# P01R0.net
KiCad netlist of a schematic drawn in EAGLE
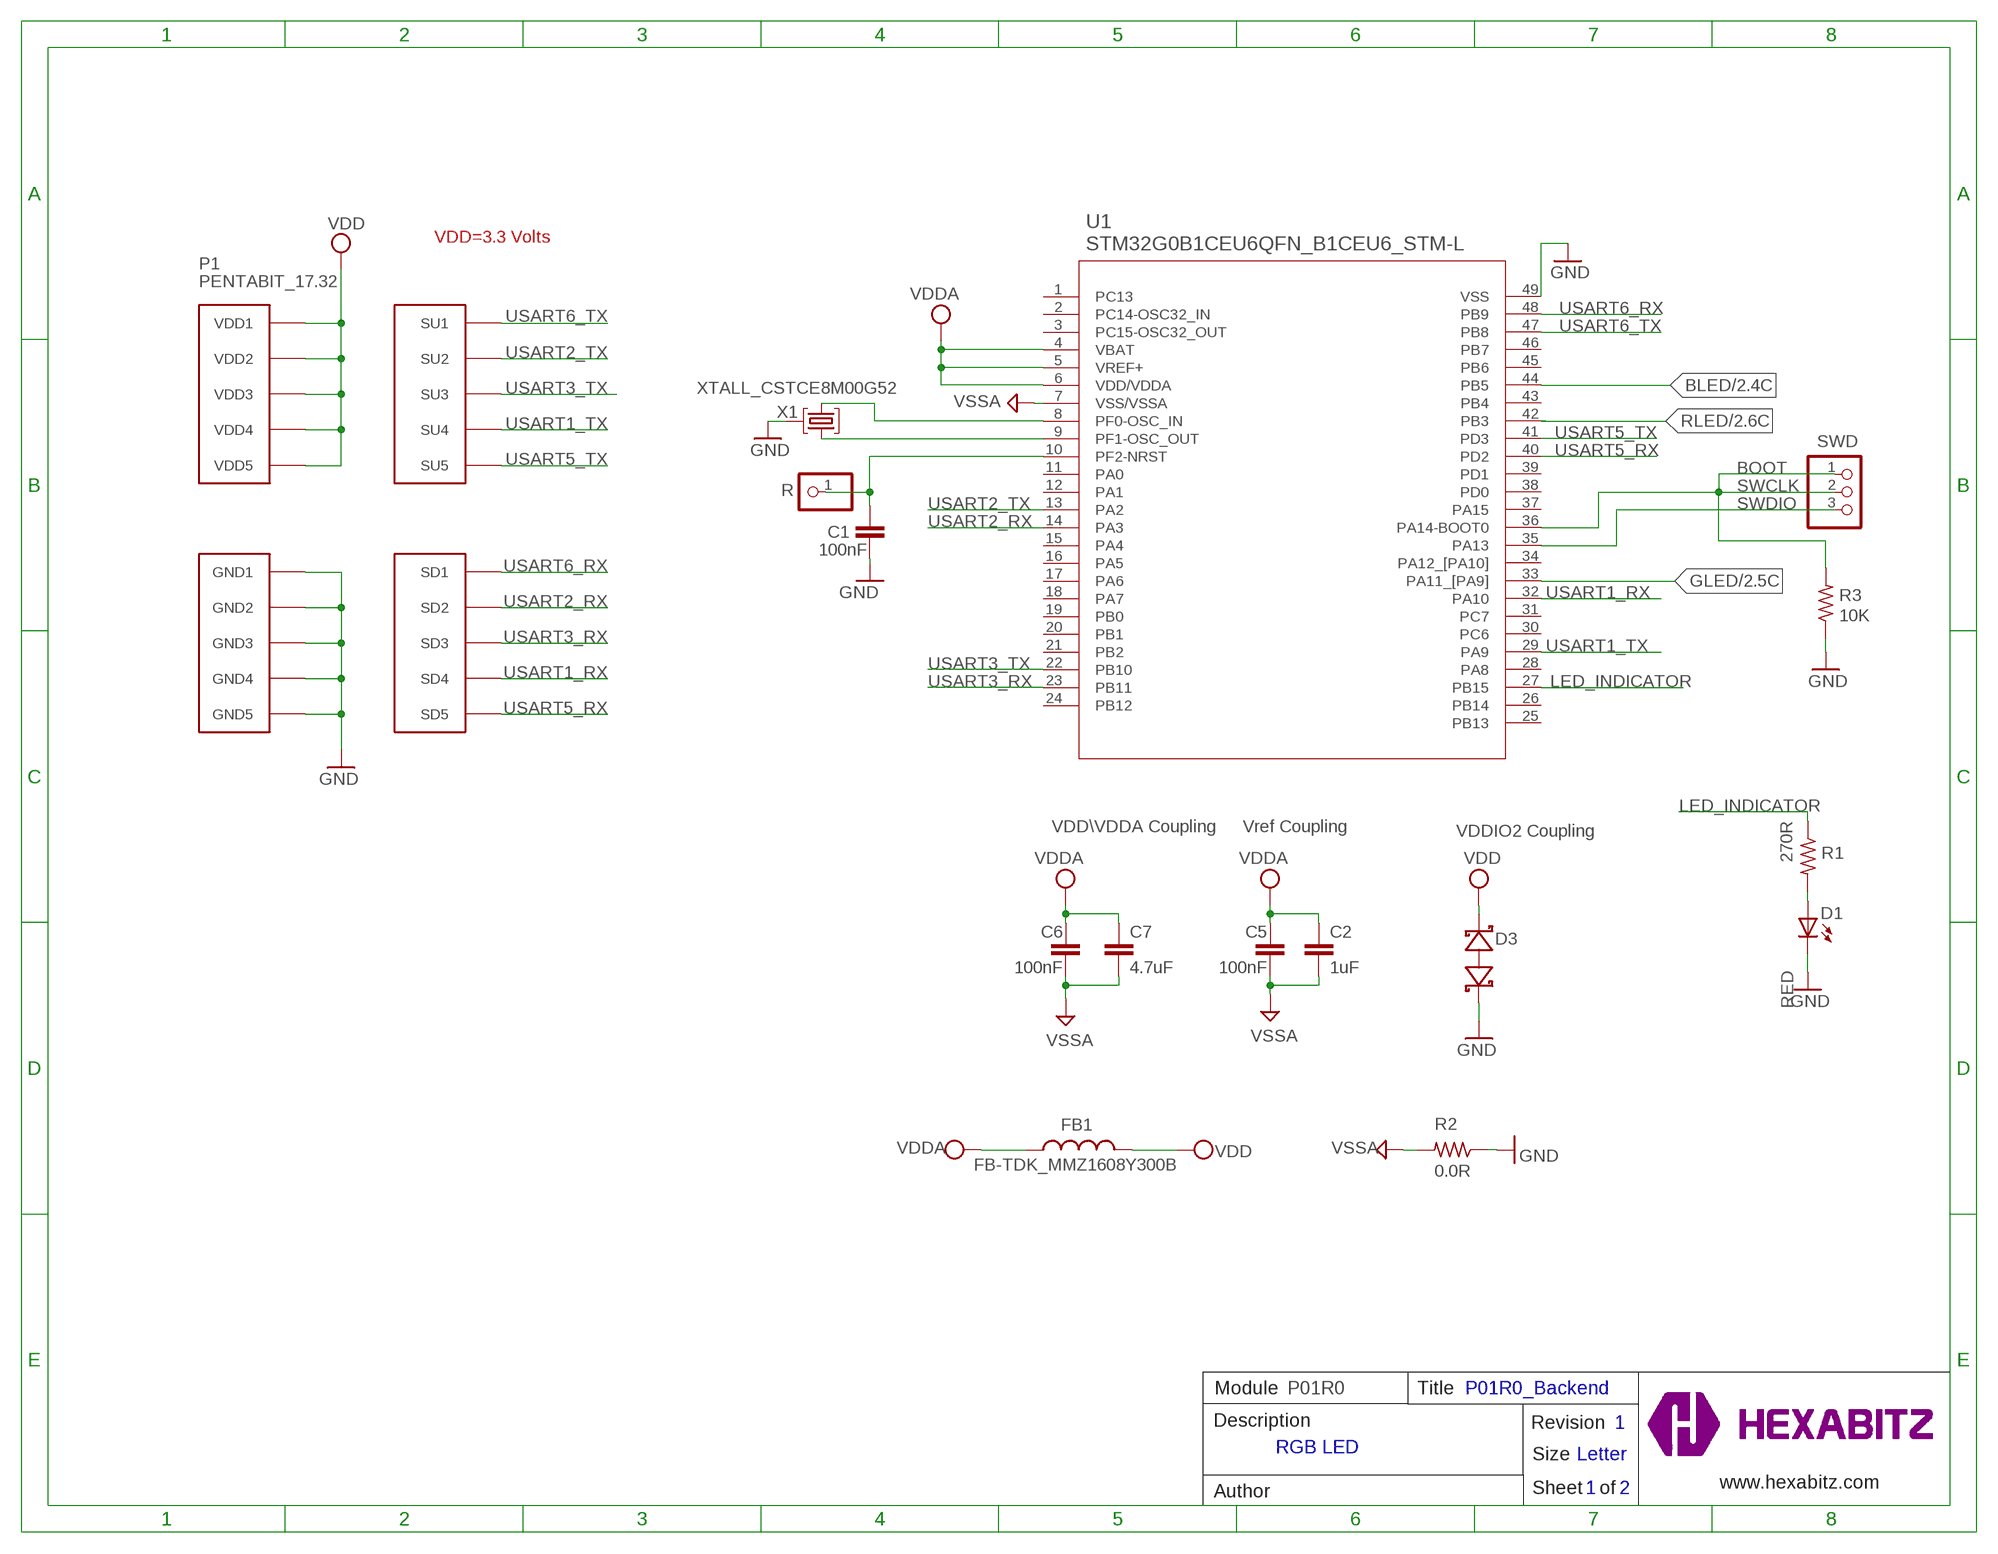
[diagram p0: schematic, sheet 1]
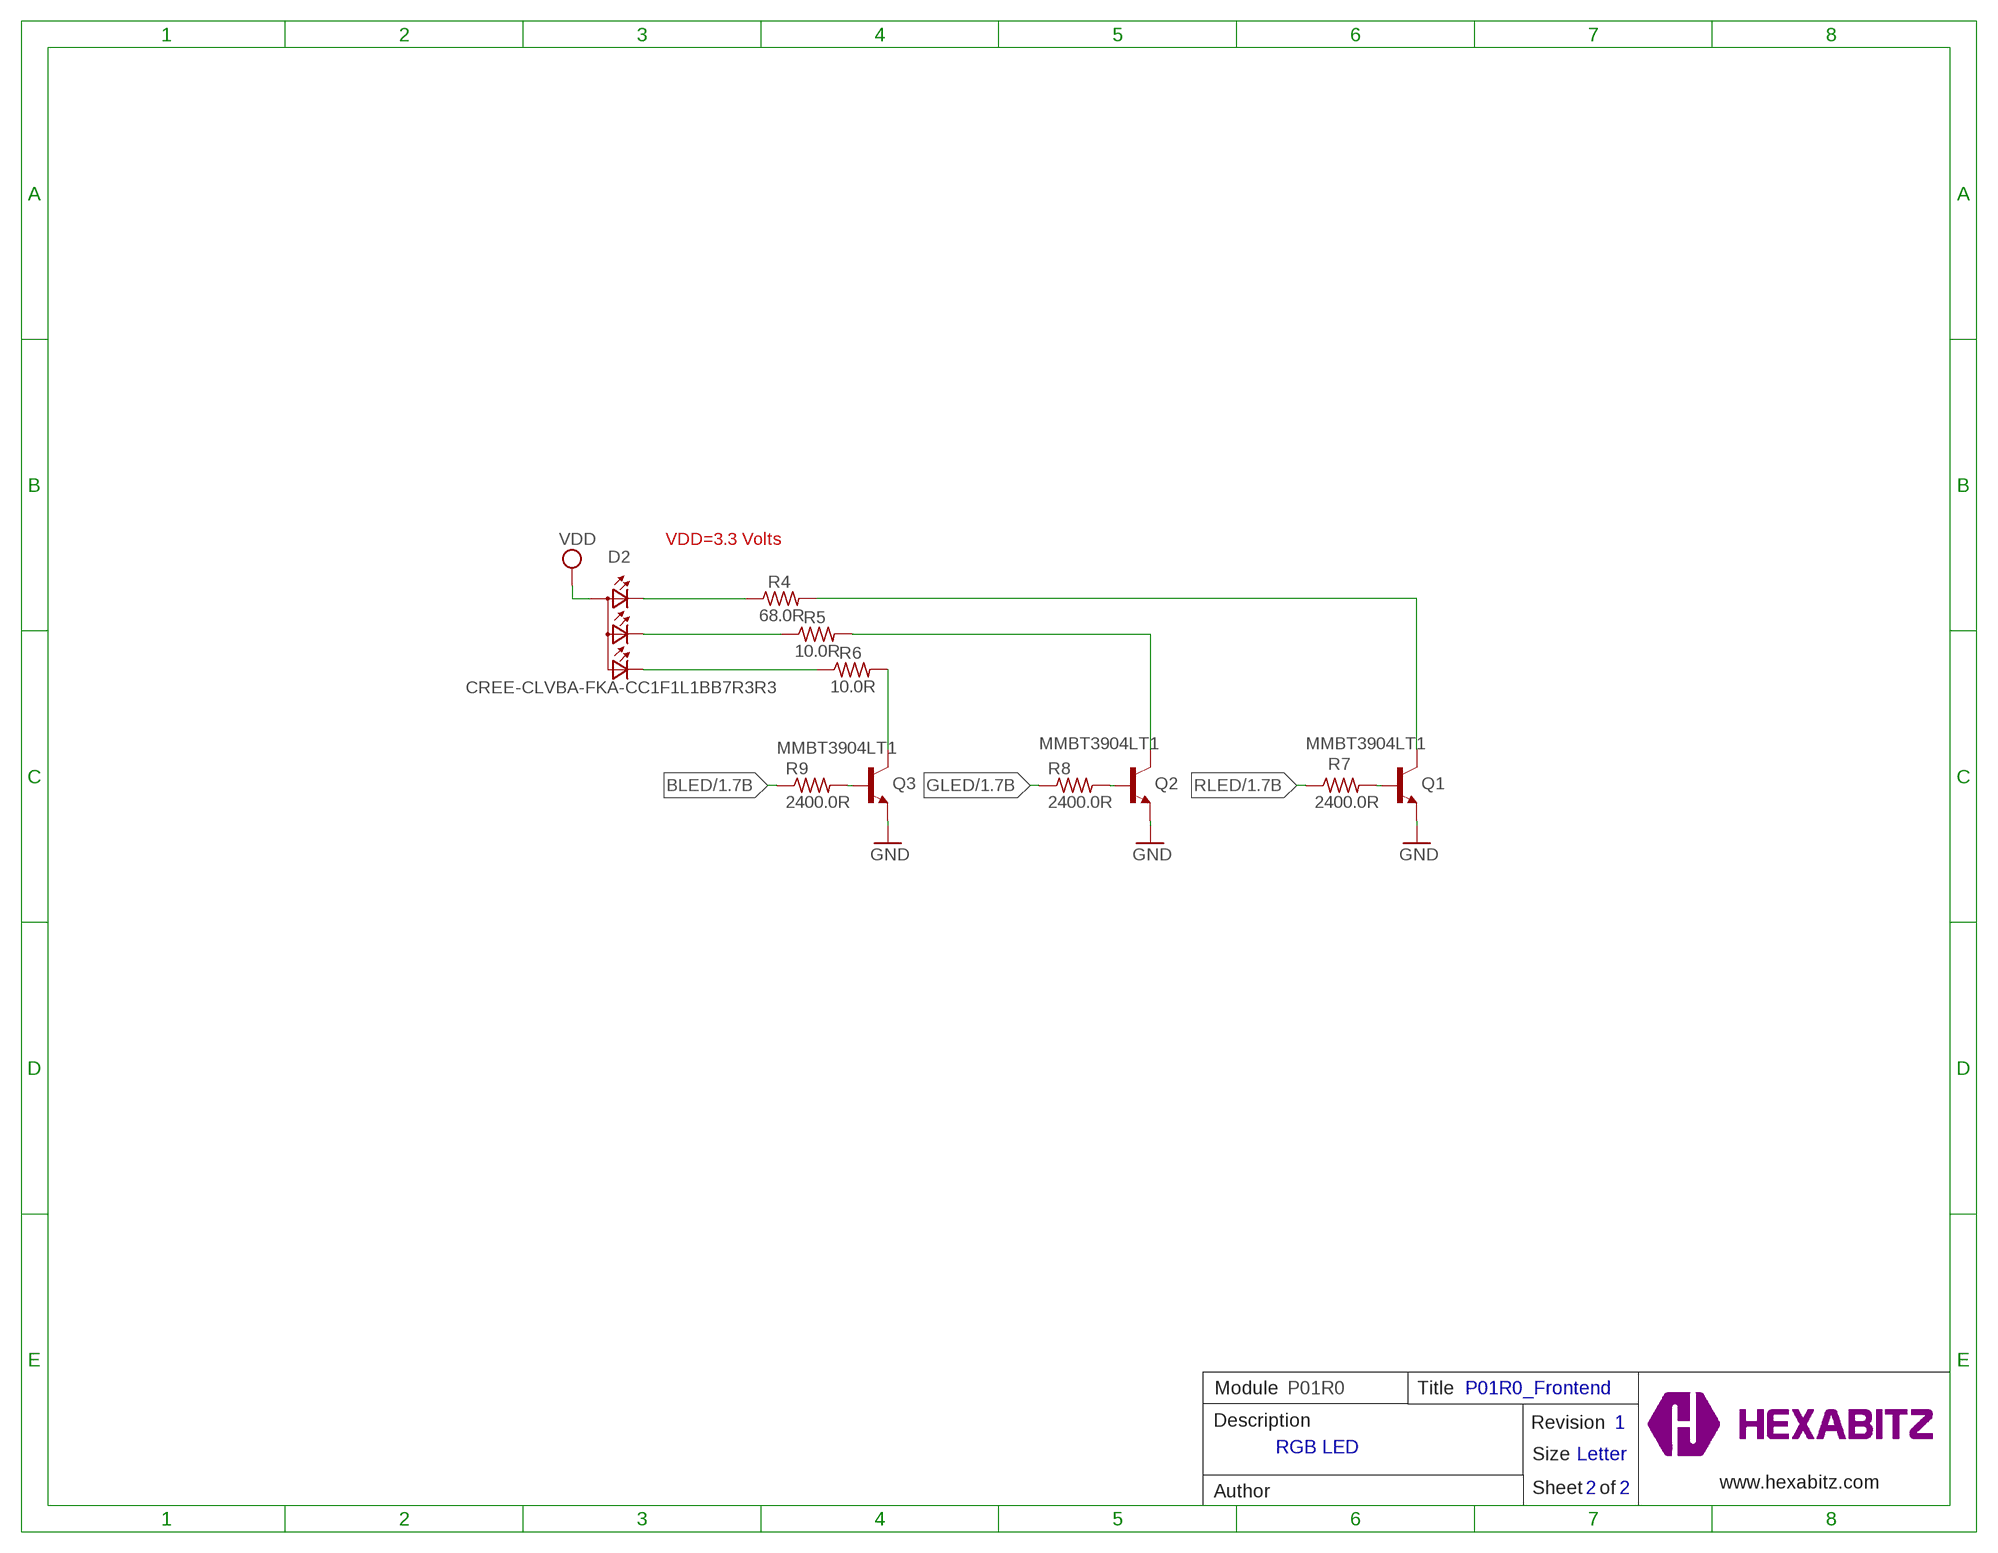
[diagram p1: schematic, sheet 2]

(export (version "E")
  (design (tool "Eeschema 10.0.6"))
  (components
    (comp (ref "C1")
      (value "100nF")
      (footprint "eagle-import:C-0603")
      (libsource (lib "eagle-import") (part "C-0603"))
    )
    (comp (ref "C2")
      (value "1uF")
      (footprint "eagle-import:C-0805")
      (libsource (lib "eagle-import") (part "C-0805"))
    )
    (comp (ref "C5")
      (value "100nF")
      (footprint "eagle-import:C-0603")
      (libsource (lib "eagle-import") (part "C-0603"))
    )
    (comp (ref "C6")
      (value "100nF")
      (footprint "eagle-import:C-0603")
      (libsource (lib "eagle-import") (part "C-0603"))
    )
    (comp (ref "C7")
      (value "4.7uF")
      (footprint "eagle-import:C-0805")
      (libsource (lib "eagle-import") (part "C-0805"))
    )
    (comp (ref "D1")
      (value "RED")
      (footprint "eagle-import:VLMS1300-GS08")
      (fields
        (field (name "MPN") "VLMS1300-GS08")
        (field (name "MFN") "Vishay")
        (field (name "MPN_1") "VLMS1300-GS08")
        (field (name "OCTOPART_URL") "https://octopart.com/vlms1300-gs08-vishay-21709201?r=sp&s=_gcP4_q8T1SC6PJQPTQ9yA")
      )
      (libsource (lib "eagle-import") (part "VLMS1300-GS08"))
    )
    (comp (ref "D3")
      (value "BOURNS_CDSOD323-T03SCBOURNS_CDSOD323-T03SC_0_0")
      (footprint "eagle-import:BOURNS_CDSOD323-T03SC_0")
      (fields (field (name "MPN") "CDSOD323-T03SC"))
      (libsource (lib "eagle-import") (part "BOURNS_CDSOD323-T03SCBOURNS_CDSOD323-T03SC_0_0"))
    )
    (comp (ref "FB1")
      (value "FB-TDK_MMZ1608Y300B")
      (footprint "eagle-import:FB-0603")
      (fields
        (field (name "MFN") "TDK ")
        (field (name "MPN") "MMZ1608Y300B")
        (field (name "OCTOPART_URL") "https://octopart.com/mmz1608y300b-tdk-368280?r=sp&s=cd9_2ZEqQ9q9UNBuQgHAiA")
      )
      (libsource (lib "eagle-import") (part "FB-0603"))
    )
    (comp (ref "P1")
      (value "PENTABIT_17.32")
      (footprint "eagle-import:PENTABIT_17.32")
      (libsource (lib "eagle-import") (part "PENTABIT_?17.32"))
    )
    (comp (ref "R")
      (value "R")
      (footprint "eagle-import:1X01")
      (fields (field (name "MPN") "87227-1"))
      (libsource (lib "eagle-import") (part "PINHD-1X1"))
    )
    (comp (ref "R1")
      (value "270R")
      (footprint "eagle-import:R-0603")
      (libsource (lib "eagle-import") (part "R-0603"))
    )
    (comp (ref "R2")
      (value "0.0R")
      (footprint "eagle-import:R-0603")
      (fields
        (field (name "MFN") "Yageo")
        (field (name "MPN") "RC0603JR-070RL")
        (field (name "OCTOPART_URL") "https://octopart.com/rc0603jr-070rl-yageo-1241539?r=sp&s=X2NteqRjRNWrnx42Y0aliA")
        (field (name "RESISTANCE") "0.0 Ohm")
      )
      (libsource (lib "eagle-import") (part "R-0603"))
    )
    (comp (ref "R3")
      (value "10K")
      (footprint "eagle-import:R-0603")
      (libsource (lib "eagle-import") (part "R-0603"))
    )
    (comp (ref "SWD")
      (value "PINHD-1X3")
      (footprint "eagle-import:1X03")
      (libsource (lib "eagle-import") (part "PINHD-1X3"))
    )
    (comp (ref "U1")
      (value "STM32G0B1CEU6QFN_B1CEU6_STM-L")
      (footprint "eagle-import:QFN_B1CEU6_STM-L")
      (fields
        (field (name "MANUFACTURER_PART_NUMBER") "STM32G0B1CEU6")
        (field (name "COPYRIGHT") "Copyright (C) 2021 Ultra Librarian. All rights reserved.")
      )
      (libsource (lib "eagle-import") (part "STM32G0B1CEU6QFN_B1CEU6_STM-L"))
    )
    (comp (ref "X1")
      (value "XTALL_CSTCE8M00G52")
      (footprint "eagle-import:XTALL_CSTCE8M00G52")
      (fields (field (name "MPN") "CSTCE8M00G52Z-R0"))
      (libsource (lib "eagle-import") (part "XTALL_CSTCE8M00G52"))
    )
    (comp (ref "D2")
      (value "CREE-CLVBA-FKA-CC1F1L1BB7R3R3")
      (footprint "eagle-import:PCB-1023943-1")
      (fields (field (name "MPN") "CLVBA-FKA-CC1F1L1BB7R3R3"))
      (libsource (lib "eagle-import") (part "CREE-CLVBA-FKA-CC1F1L1BB7R3R3"))
    )
    (comp (ref "Q1")
      (value "MMBT3904LT1")
      (footprint "eagle-import:MMBT3904LT1")
      (fields
        (field (name "OCTOPART_ID") "0bb6c2bc2200d471")
        (field (name "OCTOPART_URL") "http://octopart.com/mmbt3904lt1g-on+semiconductor-3280")
        (field (name "POLARITY") "NPN")
        (field (name "POWER_DISSIPATION") "0.225W")
        (field (name "VOLTAGE_RATING_DC") "40.0V")
      )
      (libsource (lib "eagle-import") (part "MMBT3904LT1"))
    )
    (comp (ref "Q2")
      (value "MMBT3904LT1")
      (footprint "eagle-import:MMBT3904LT1")
      (fields
        (field (name "OCTOPART_ID") "0bb6c2bc2200d471")
        (field (name "OCTOPART_URL") "http://octopart.com/mmbt3904lt1g-on+semiconductor-3280")
        (field (name "POLARITY") "NPN")
        (field (name "POWER_DISSIPATION") "0.225W")
        (field (name "VOLTAGE_RATING_DC") "40.0V")
      )
      (libsource (lib "eagle-import") (part "MMBT3904LT1"))
    )
    (comp (ref "Q3")
      (value "MMBT3904LT1")
      (footprint "eagle-import:MMBT3904LT1")
      (fields
        (field (name "MFN") "ON Semiconductor")
        (field (name "MPN") "MMBT3904LT1G")
        (field (name "OCTOPART_ID") "0bb6c2bc2200d471")
        (field (name "OCTOPART_URL") "http://octopart.com/mmbt3904lt1g-on+semiconductor-3280")
        (field (name "POLARITY") "NPN")
        (field (name "POWER_DISSIPATION") "0.225W")
        (field (name "VOLTAGE_RATING_DC") "40.0V")
      )
      (libsource (lib "eagle-import") (part "MMBT3904LT1"))
    )
    (comp (ref "R4")
      (value "68.0R")
      (footprint "eagle-import:R-0603")
      (fields
        (field (name "MFN") "Vishay")
        (field (name "MPN") "CRCW060368R0FKEA")
        (field (name "OCTOPART_URL") "https://octopart.com/crcw060368r0fkea-vishay-39811903")
        (field (name "RESISTANCE") "68.0 Ω")
        (field (name "SPICEPREFIX") "R")
        (field (name "TOLERANCE") "1%")
      )
      (libsource (lib "eagle-import") (part "R-0603"))
    )
    (comp (ref "R5")
      (value "10.0R")
      (footprint "eagle-import:R-0603")
      (fields
        (field (name "MFN") "Vishay")
        (field (name "MPN") "CRCW060310R0FKEB")
        (field (name "OCTOPART_URL") "https://octopart.com/crcw060310r0fkeb-vishay-42507905")
        (field (name "RESISTANCE") "10.0 Ω")
        (field (name "TOLERANCE") "1%")
      )
      (libsource (lib "eagle-import") (part "R-0603"))
    )
    (comp (ref "R6")
      (value "10.0R")
      (footprint "eagle-import:R-0603")
      (fields
        (field (name "MFN") "Vishay")
        (field (name "MPN") "CRCW060310R0FKEB")
        (field (name "OCTOPART_URL") "https://octopart.com/crcw060310r0fkeb-vishay-42507905")
        (field (name "RESISTANCE") "10.0 Ω")
        (field (name "TOLERANCE") "1%")
      )
      (libsource (lib "eagle-import") (part "R-0603"))
    )
    (comp (ref "R7")
      (value "2400.0R")
      (footprint "eagle-import:R-0603")
      (fields
        (field (name "MFN") "Vishay")
        (field (name "MPN") "CRCW06032K40JNEA")
        (field (name "OCTOPART_URL") "https://octopart.com/crcw06032k40jnea-vishay-40298967")
        (field (name "RESISTANCE") "2400.0 Ω")
        (field (name "TOLERANCE") "5%")
      )
      (libsource (lib "eagle-import") (part "R-0603"))
    )
    (comp (ref "R8")
      (value "2400.0R")
      (footprint "eagle-import:R-0603")
      (fields
        (field (name "MFN") "Vishay")
        (field (name "MPN") "CRCW06032K40JNEA")
        (field (name "OCTOPART_URL") "https://octopart.com/crcw06032k40jnea-vishay-40298967")
        (field (name "RESISTANCE") "2400.0 Ω")
        (field (name "TOLERANCE") "5%")
      )
      (libsource (lib "eagle-import") (part "R-0603"))
    )
    (comp (ref "R9")
      (value "2400.0R")
      (footprint "eagle-import:R-0603")
      (fields
        (field (name "MFN") "Vishay")
        (field (name "MPN") "CRCW06032K40JNEA")
        (field (name "OCTOPART_URL") "https://octopart.com/crcw06032k40jnea-vishay-40298967")
        (field (name "TOLERANCE") "5%")
      )
      (libsource (lib "eagle-import") (part "R-0603"))
    )
    (comp (ref "TRIMBLE-LOGO1")
      (value "HEXA-LOGO")
      (footprint "eagle-import:HEXA-LOGO")
      (libsource (lib "eagle-import") (part "HEXA-LOGO"))
    )
  )
  (nets
    (net (code "1") (name "BLED") (class "Default")
      (node (ref "R9") (pin "1") (pinfunction "1_1") (pintype "passive"))
      (node (ref "U1") (pin "44") (pinfunction "PB5_44") (pintype "bidirectional"))
    )
    (net (code "2") (name "GLED") (class "Default")
      (node (ref "R8") (pin "1") (pinfunction "1_1") (pintype "passive"))
      (node (ref "U1") (pin "33") (pinfunction "PA11_[PA9]_33") (pintype "bidirectional"))
    )
    (net (code "3") (name "GND") (class "Default")
      (node (ref "C1") (pin "2") (pinfunction "2_2") (pintype "passive"))
      (node (ref "D1") (pin "C") (pinfunction "C_C") (pintype "passive"))
      (node (ref "D3") (pin "1") (pinfunction "A_1") (pintype "passive"))
      (node (ref "P1") (pin "PAD_PD10") (pinfunction "GND5_PAD_PD10") (pintype "power_in"))
      (node (ref "P1") (pin "PAD_PD6") (pinfunction "GND1_PAD_PD6") (pintype "power_in"))
      (node (ref "P1") (pin "PAD_PD7") (pinfunction "GND2_PAD_PD7") (pintype "power_in"))
      (node (ref "P1") (pin "PAD_PD8") (pinfunction "GND3_PAD_PD8") (pintype "power_in"))
      (node (ref "P1") (pin "PAD_PD9") (pinfunction "GND4_PAD_PD9") (pintype "power_in"))
      (node (ref "Q1") (pin "2") (pinfunction "E_2") (pintype "passive"))
      (node (ref "Q2") (pin "2") (pinfunction "E_2") (pintype "passive"))
      (node (ref "Q3") (pin "2") (pinfunction "E_2") (pintype "passive"))
      (node (ref "R2") (pin "1") (pinfunction "1_1") (pintype "passive"))
      (node (ref "R3") (pin "1") (pinfunction "1_1") (pintype "passive"))
      (node (ref "U1") (pin "49") (pinfunction "VSS_49") (pintype "passive"))
      (node (ref "X1") (pin "P$2") (pinfunction "2_P$2") (pintype "passive"))
    )
    (net (code "4") (name "LED_INDICATOR") (class "Default")
      (node (ref "R1") (pin "1") (pinfunction "1_1") (pintype "passive"))
      (node (ref "U1") (pin "27") (pinfunction "PB15_27") (pintype "bidirectional"))
    )
    (net (code "5") (name "Net-(D1-PadA)") (class "Default")
      (node (ref "D1") (pin "A") (pinfunction "A_A") (pintype "passive"))
      (node (ref "R1") (pin "2") (pinfunction "2_2") (pintype "passive"))
    )
    (net (code "6") (name "Net-(D2-CBLUE)") (class "Default")
      (node (ref "D2") (pin "P$3") (pinfunction "CBLUE_P$3") (pintype "passive"))
      (node (ref "R6") (pin "1") (pinfunction "1_1") (pintype "passive"))
    )
    (net (code "7") (name "Net-(D2-CGREEN)") (class "Default")
      (node (ref "D2") (pin "P$4") (pinfunction "CGREEN_P$4") (pintype "passive"))
      (node (ref "R5") (pin "1") (pinfunction "1_1") (pintype "passive"))
    )
    (net (code "8") (name "Net-(D2-CRED)") (class "Default")
      (node (ref "D2") (pin "P$1") (pinfunction "CRED_P$1") (pintype "passive"))
      (node (ref "R4") (pin "1") (pinfunction "1_1") (pintype "passive"))
    )
    (net (code "9") (name "Net-(Q1-B)") (class "Default")
      (node (ref "Q1") (pin "1") (pinfunction "B_1") (pintype "passive"))
      (node (ref "R7") (pin "2") (pinfunction "2_2") (pintype "passive"))
    )
    (net (code "10") (name "Net-(Q1-C)") (class "Default")
      (node (ref "Q1") (pin "3") (pinfunction "C_3") (pintype "passive"))
      (node (ref "R4") (pin "2") (pinfunction "2_2") (pintype "passive"))
    )
    (net (code "11") (name "Net-(Q2-B)") (class "Default")
      (node (ref "Q2") (pin "1") (pinfunction "B_1") (pintype "passive"))
      (node (ref "R8") (pin "2") (pinfunction "2_2") (pintype "passive"))
    )
    (net (code "12") (name "Net-(Q2-C)") (class "Default")
      (node (ref "Q2") (pin "3") (pinfunction "C_3") (pintype "passive"))
      (node (ref "R5") (pin "2") (pinfunction "2_2") (pintype "passive"))
    )
    (net (code "13") (name "Net-(Q3-B)") (class "Default")
      (node (ref "Q3") (pin "1") (pinfunction "B_1") (pintype "passive"))
      (node (ref "R9") (pin "2") (pinfunction "2_2") (pintype "passive"))
    )
    (net (code "14") (name "Net-(Q3-C)") (class "Default")
      (node (ref "Q3") (pin "3") (pinfunction "C_3") (pintype "passive"))
      (node (ref "R6") (pin "2") (pinfunction "2_2") (pintype "passive"))
    )
    (net (code "15") (name "Net-(U1-PF0-OSC_IN)") (class "Default")
      (node (ref "U1") (pin "8") (pinfunction "PF0-OSC_IN_8") (pintype "bidirectional"))
      (node (ref "X1") (pin "P$3") (pinfunction "3_P$3") (pintype "passive"))
    )
    (net (code "16") (name "Net-(U1-PF1-OSC_OUT)") (class "Default")
      (node (ref "U1") (pin "9") (pinfunction "PF1-OSC_OUT_9") (pintype "output"))
      (node (ref "X1") (pin "P$1") (pinfunction "1_P$1") (pintype "passive"))
    )
    (net (code "17") (name "Net-(U1-PF2-NRST)") (class "Default")
      (node (ref "C1") (pin "1") (pinfunction "1_1") (pintype "passive"))
      (node (ref "R") (pin "1") (pinfunction "1_1") (pintype "passive"))
      (node (ref "U1") (pin "10") (pinfunction "PF2-NRST_10") (pintype "bidirectional"))
    )
    (net (code "18") (name "RLED") (class "Default")
      (node (ref "R7") (pin "1") (pinfunction "1_1") (pintype "passive"))
      (node (ref "U1") (pin "42") (pinfunction "PB3_42") (pintype "bidirectional"))
    )
    (net (code "19") (name "SWCLK") (class "Default")
      (node (ref "R3") (pin "2") (pinfunction "2_2") (pintype "passive"))
      (node (ref "SWD") (pin "1") (pinfunction "1_1") (pintype "passive"))
      (node (ref "SWD") (pin "2") (pinfunction "2_2") (pintype "passive"))
      (node (ref "U1") (pin "36") (pinfunction "PA14-BOOT0_36") (pintype "bidirectional"))
    )
    (net (code "20") (name "SWDIO") (class "Default")
      (node (ref "SWD") (pin "3") (pinfunction "3_3") (pintype "passive"))
      (node (ref "U1") (pin "35") (pinfunction "PA13_35") (pintype "bidirectional"))
    )
    (net (code "21") (name "USART1_RX") (class "Default")
      (node (ref "P1") (pin "PAD_PD4") (pinfunction "SD4_PAD_PD4") (pintype "bidirectional"))
      (node (ref "U1") (pin "32") (pinfunction "PA10_32") (pintype "bidirectional"))
    )
    (net (code "22") (name "USART1_TX") (class "Default")
      (node (ref "P1") (pin "PAD_PU4") (pinfunction "SU4_PAD_PU4") (pintype "bidirectional"))
      (node (ref "U1") (pin "29") (pinfunction "PA9_29") (pintype "bidirectional"))
    )
    (net (code "23") (name "USART2_RX") (class "Default")
      (node (ref "P1") (pin "PAD_PD2") (pinfunction "SD2_PAD_PD2") (pintype "bidirectional"))
      (node (ref "U1") (pin "14") (pinfunction "PA3_14") (pintype "bidirectional"))
    )
    (net (code "24") (name "USART2_TX") (class "Default")
      (node (ref "P1") (pin "PAD_PU2") (pinfunction "SU2_PAD_PU2") (pintype "bidirectional"))
      (node (ref "U1") (pin "13") (pinfunction "PA2_13") (pintype "bidirectional"))
    )
    (net (code "25") (name "USART3_RX") (class "Default")
      (node (ref "P1") (pin "PAD_PD3") (pinfunction "SD3_PAD_PD3") (pintype "bidirectional"))
      (node (ref "U1") (pin "23") (pinfunction "PB11_23") (pintype "bidirectional"))
    )
    (net (code "26") (name "USART3_TX") (class "Default")
      (node (ref "P1") (pin "PAD_PU3") (pinfunction "SU3_PAD_PU3") (pintype "bidirectional"))
      (node (ref "U1") (pin "22") (pinfunction "PB10_22") (pintype "bidirectional"))
    )
    (net (code "27") (name "USART5_RX") (class "Default")
      (node (ref "P1") (pin "PAD_PD5") (pinfunction "SD5_PAD_PD5") (pintype "bidirectional"))
      (node (ref "U1") (pin "40") (pinfunction "PD2_40") (pintype "bidirectional"))
    )
    (net (code "28") (name "USART5_TX") (class "Default")
      (node (ref "P1") (pin "PAD_PU5") (pinfunction "SU5_PAD_PU5") (pintype "bidirectional"))
      (node (ref "U1") (pin "41") (pinfunction "PD3_41") (pintype "bidirectional"))
    )
    (net (code "29") (name "USART6_RX") (class "Default")
      (node (ref "P1") (pin "PAD_PD1") (pinfunction "SD1_PAD_PD1") (pintype "bidirectional"))
      (node (ref "U1") (pin "48") (pinfunction "PB9_48") (pintype "bidirectional"))
    )
    (net (code "30") (name "USART6_TX") (class "Default")
      (node (ref "P1") (pin "PAD_PU1") (pinfunction "SU1_PAD_PU1") (pintype "bidirectional"))
      (node (ref "U1") (pin "47") (pinfunction "PB8_47") (pintype "bidirectional"))
    )
    (net (code "31") (name "VDD") (class "Default")
      (node (ref "D2") (pin "P$2") (pinfunction "A2_P$2") (pintype "passive"))
      (node (ref "D3") (pin "2") (pinfunction "C_2") (pintype "passive"))
      (node (ref "FB1") (pin "2") (pinfunction "2_2") (pintype "passive"))
      (node (ref "P1") (pin "PAD_PU10") (pinfunction "VDD5_PAD_PU10") (pintype "power_in"))
      (node (ref "P1") (pin "PAD_PU6") (pinfunction "VDD1_PAD_PU6") (pintype "power_in"))
      (node (ref "P1") (pin "PAD_PU7") (pinfunction "VDD2_PAD_PU7") (pintype "power_in"))
      (node (ref "P1") (pin "PAD_PU8") (pinfunction "VDD3_PAD_PU8") (pintype "power_in"))
      (node (ref "P1") (pin "PAD_PU9") (pinfunction "VDD4_PAD_PU9") (pintype "power_in"))
    )
    (net (code "32") (name "VDDA") (class "Default")
      (node (ref "C2") (pin "1") (pinfunction "1_1") (pintype "passive"))
      (node (ref "C5") (pin "1") (pinfunction "1_1") (pintype "passive"))
      (node (ref "C6") (pin "1") (pinfunction "1_1") (pintype "passive"))
      (node (ref "C7") (pin "1") (pinfunction "1_1") (pintype "passive"))
      (node (ref "FB1") (pin "1") (pinfunction "1_1") (pintype "passive"))
      (node (ref "U1") (pin "4") (pinfunction "VBAT_4") (pintype "passive"))
      (node (ref "U1") (pin "5") (pinfunction "VREF+_5") (pintype "power_in"))
      (node (ref "U1") (pin "6") (pinfunction "VDD/VDDA_6") (pintype "power_in"))
    )
    (net (code "33") (name "VSSA") (class "Default")
      (node (ref "C2") (pin "2") (pinfunction "2_2") (pintype "passive"))
      (node (ref "C5") (pin "2") (pinfunction "2_2") (pintype "passive"))
      (node (ref "C6") (pin "2") (pinfunction "2_2") (pintype "passive"))
      (node (ref "C7") (pin "2") (pinfunction "2_2") (pintype "passive"))
      (node (ref "R2") (pin "2") (pinfunction "2_2") (pintype "passive"))
      (node (ref "U1") (pin "7") (pinfunction "VSS/VSSA_7") (pintype "passive"))
    )
    (net (code "34") (name "unconnected-(U1-PA0-Pad11)") (class "Default")
      (node (ref "U1") (pin "11") (pinfunction "PA0_11") (pintype "bidirectional"))
    )
    (net (code "35") (name "unconnected-(U1-PA1-Pad12)") (class "Default")
      (node (ref "U1") (pin "12") (pinfunction "PA1_12") (pintype "bidirectional"))
    )
    (net (code "36") (name "unconnected-(U1-PA4-Pad15)") (class "Default")
      (node (ref "U1") (pin "15") (pinfunction "PA4_15") (pintype "bidirectional"))
    )
    (net (code "37") (name "unconnected-(U1-PA5-Pad16)") (class "Default")
      (node (ref "U1") (pin "16") (pinfunction "PA5_16") (pintype "bidirectional"))
    )
    (net (code "38") (name "unconnected-(U1-PA6-Pad17)") (class "Default")
      (node (ref "U1") (pin "17") (pinfunction "PA6_17") (pintype "bidirectional"))
    )
    (net (code "39") (name "unconnected-(U1-PA7-Pad18)") (class "Default")
      (node (ref "U1") (pin "18") (pinfunction "PA7_18") (pintype "bidirectional"))
    )
    (net (code "40") (name "unconnected-(U1-PA8-Pad28)") (class "Default")
      (node (ref "U1") (pin "28") (pinfunction "PA8_28") (pintype "bidirectional"))
    )
    (net (code "41") (name "unconnected-(U1-PA12_[PA10]-Pad34)") (class "Default")
      (node (ref "U1") (pin "34") (pinfunction "PA12_[PA10]_34") (pintype "bidirectional"))
    )
    (net (code "42") (name "unconnected-(U1-PA15-Pad37)") (class "Default")
      (node (ref "U1") (pin "37") (pinfunction "PA15_37") (pintype "bidirectional"))
    )
    (net (code "43") (name "unconnected-(U1-PB0-Pad19)") (class "Default")
      (node (ref "U1") (pin "19") (pinfunction "PB0_19") (pintype "bidirectional"))
    )
    (net (code "44") (name "unconnected-(U1-PB1-Pad20)") (class "Default")
      (node (ref "U1") (pin "20") (pinfunction "PB1_20") (pintype "bidirectional"))
    )
    (net (code "45") (name "unconnected-(U1-PB2-Pad21)") (class "Default")
      (node (ref "U1") (pin "21") (pinfunction "PB2_21") (pintype "bidirectional"))
    )
    (net (code "46") (name "unconnected-(U1-PB4-Pad43)") (class "Default")
      (node (ref "U1") (pin "43") (pinfunction "PB4_43") (pintype "bidirectional"))
    )
    (net (code "47") (name "unconnected-(U1-PB6-Pad45)") (class "Default")
      (node (ref "U1") (pin "45") (pinfunction "PB6_45") (pintype "bidirectional"))
    )
    (net (code "48") (name "unconnected-(U1-PB7-Pad46)") (class "Default")
      (node (ref "U1") (pin "46") (pinfunction "PB7_46") (pintype "bidirectional"))
    )
    (net (code "49") (name "unconnected-(U1-PB12-Pad24)") (class "Default")
      (node (ref "U1") (pin "24") (pinfunction "PB12_24") (pintype "bidirectional"))
    )
    (net (code "50") (name "unconnected-(U1-PB13-Pad25)") (class "Default")
      (node (ref "U1") (pin "25") (pinfunction "PB13_25") (pintype "bidirectional"))
    )
    (net (code "51") (name "unconnected-(U1-PB14-Pad26)") (class "Default")
      (node (ref "U1") (pin "26") (pinfunction "PB14_26") (pintype "bidirectional"))
    )
    (net (code "52") (name "unconnected-(U1-PC6-Pad30)") (class "Default")
      (node (ref "U1") (pin "30") (pinfunction "PC6_30") (pintype "bidirectional"))
    )
    (net (code "53") (name "unconnected-(U1-PC7-Pad31)") (class "Default")
      (node (ref "U1") (pin "31") (pinfunction "PC7_31") (pintype "bidirectional"))
    )
    (net (code "54") (name "unconnected-(U1-PC13-Pad1)") (class "Default")
      (node (ref "U1") (pin "1") (pinfunction "PC13_1") (pintype "bidirectional"))
    )
    (net (code "55") (name "unconnected-(U1-PC14-OSC32_IN-Pad2)") (class "Default")
      (node (ref "U1") (pin "2") (pinfunction "PC14-OSC32_IN_2") (pintype "bidirectional"))
    )
    (net (code "56") (name "unconnected-(U1-PC15-OSC32_OUT-Pad3)") (class "Default")
      (node (ref "U1") (pin "3") (pinfunction "PC15-OSC32_OUT_3") (pintype "output"))
    )
    (net (code "57") (name "unconnected-(U1-PD0-Pad38)") (class "Default")
      (node (ref "U1") (pin "38") (pinfunction "PD0_38") (pintype "bidirectional"))
    )
    (net (code "58") (name "unconnected-(U1-PD1-Pad39)") (class "Default")
      (node (ref "U1") (pin "39") (pinfunction "PD1_39") (pintype "bidirectional"))
    )
  )
)
